# rtc_lcd.net
KiCad netlist of a schematic drawn in EAGLE
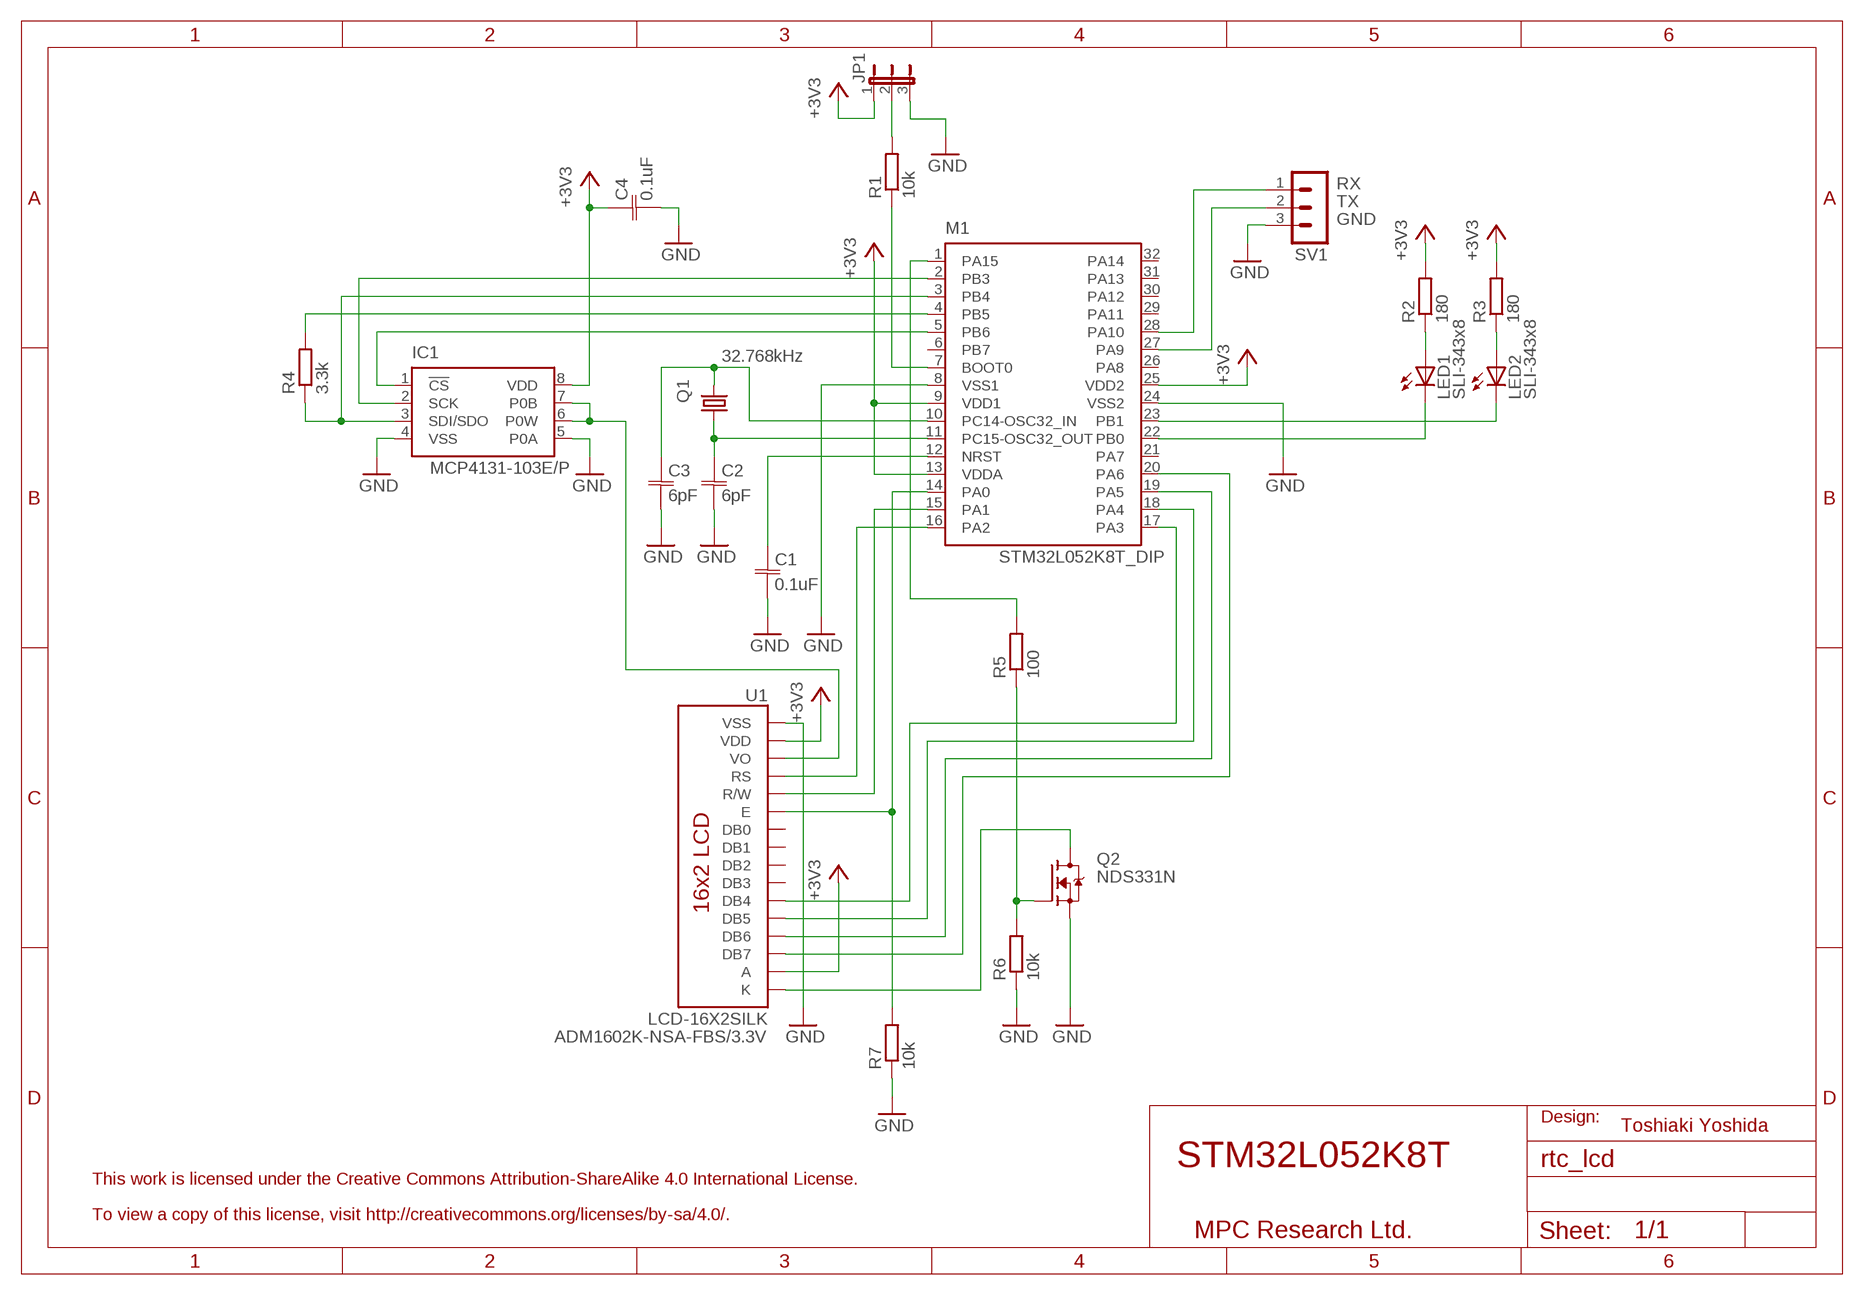
[diagram p0: schematic, sheet 1]

(export (version "E")
  (design (tool "Eeschema 10.0.6"))
  (components
    (comp (ref "C1")
      (value "0.1uF")
      (footprint "eagle-import:C050-024X044")
      (libsource (lib "eagle-import") (part "C-JIS050-024X044"))
    )
    (comp (ref "C2")
      (value "6pF")
      (footprint "eagle-import:C050-024X044")
      (libsource (lib "eagle-import") (part "C-JIS050-024X044"))
    )
    (comp (ref "C3")
      (value "6pF")
      (footprint "eagle-import:C050-024X044")
      (libsource (lib "eagle-import") (part "C-JIS050-024X044"))
    )
    (comp (ref "C4")
      (value "0.1uF")
      (footprint "eagle-import:C050-024X044")
      (libsource (lib "eagle-import") (part "C-JIS050-024X044"))
    )
    (comp (ref "IC1")
      (value "MCP4131-103E/P")
      (footprint "eagle-import:DIL8")
      (libsource (lib "eagle-import") (part "MCP4131/P-103E"))
    )
    (comp (ref "JP1")
      (value "JP2E")
      (footprint "eagle-import:JP2")
      (libsource (lib "eagle-import") (part "JP2E"))
    )
    (comp (ref "LED1")
      (value "SLI-343x8")
      (footprint "eagle-import:LED3MM")
      (libsource (lib "eagle-import") (part "LED3MM"))
    )
    (comp (ref "LED2")
      (value "SLI-343x8")
      (footprint "eagle-import:LED3MM")
      (libsource (lib "eagle-import") (part "LED3MM"))
    )
    (comp (ref "M1")
      (value "STM32L052K8T_DIP")
      (footprint "eagle-import:DIP32")
      (libsource (lib "eagle-import") (part "STM32L052K8T_DIP"))
    )
    (comp (ref "Q1")
      (value "32.768kHz")
      (footprint "eagle-import:TC26V")
      (libsource (lib "eagle-import") (part "CRYSTALTC26V"))
    )
    (comp (ref "Q2")
      (value "NDS331N")
      (footprint "eagle-import:SOT23")
      (libsource (lib "eagle-import") (part "NDS331N"))
    )
    (comp (ref "R1")
      (value "10k")
      (footprint "eagle-import:0207_2V")
      (libsource (lib "eagle-import") (part "R-EU_0207/2V"))
    )
    (comp (ref "R2")
      (value "180")
      (footprint "eagle-import:0207_2V")
      (libsource (lib "eagle-import") (part "R-EU_0207/2V"))
    )
    (comp (ref "R3")
      (value "180")
      (footprint "eagle-import:0207_2V")
      (libsource (lib "eagle-import") (part "R-EU_0207/2V"))
    )
    (comp (ref "R4")
      (value "3.3k")
      (footprint "eagle-import:0207_2V")
      (libsource (lib "eagle-import") (part "R-EU_0207/2V"))
    )
    (comp (ref "R5")
      (value "100")
      (footprint "eagle-import:0207_2V")
      (libsource (lib "eagle-import") (part "R-EU_0207/2V"))
    )
    (comp (ref "R6")
      (value "10k")
      (footprint "eagle-import:0207_2V")
      (libsource (lib "eagle-import") (part "R-EU_0207/2V"))
    )
    (comp (ref "R7")
      (value "10k")
      (footprint "eagle-import:0207_2V")
      (libsource (lib "eagle-import") (part "R-EU_0207/2V"))
    )
    (comp (ref "SV1")
      (value "MA03-1")
      (footprint "eagle-import:MA03-1")
      (libsource (lib "eagle-import") (part "MA03-1"))
    )
    (comp (ref "U1")
      (value "LCD-16X2SILK")
      (footprint "eagle-import:LCD-16X2")
      (libsource (lib "eagle-import") (part "LCD-16X2SILK"))
    )
  )
  (nets
    (net (code "1") (name "+3V3") (class "Default")
      (node (ref "C4") (pin "1") (pinfunction "1_1") (pintype "passive"))
      (node (ref "IC1") (pin "8") (pinfunction "VDD_8") (pintype "power_in"))
      (node (ref "JP1") (pin "1") (pinfunction "1_1") (pintype "passive"))
      (node (ref "M1") (pin "13") (pinfunction "VDDA_13") (pintype "power_in"))
      (node (ref "M1") (pin "25") (pinfunction "VDD2_25") (pintype "bidirectional"))
      (node (ref "M1") (pin "9") (pinfunction "VDD1_9") (pintype "power_in"))
      (node (ref "R2") (pin "2") (pinfunction "2_2") (pintype "passive"))
      (node (ref "R3") (pin "2") (pinfunction "2_2") (pintype "passive"))
      (node (ref "U1") (pin "15") (pinfunction "A_15") (pintype "power_in"))
      (node (ref "U1") (pin "2") (pinfunction "VDD_2") (pintype "power_in"))
    )
    (net (code "2") (name "GND") (class "Default")
      (node (ref "C1") (pin "2") (pinfunction "2_2") (pintype "passive"))
      (node (ref "C2") (pin "2") (pinfunction "2_2") (pintype "passive"))
      (node (ref "C3") (pin "2") (pinfunction "2_2") (pintype "passive"))
      (node (ref "C4") (pin "2") (pinfunction "2_2") (pintype "passive"))
      (node (ref "IC1") (pin "4") (pinfunction "VSS_4") (pintype "power_in"))
      (node (ref "IC1") (pin "5") (pinfunction "P0A_5") (pintype "passive"))
      (node (ref "JP1") (pin "3") (pinfunction "3_3") (pintype "passive"))
      (node (ref "M1") (pin "24") (pinfunction "VSS2_24") (pintype "power_in"))
      (node (ref "M1") (pin "8") (pinfunction "VSS1_8") (pintype "power_in"))
      (node (ref "Q2") (pin "2") (pinfunction "S_2") (pintype "passive"))
      (node (ref "R6") (pin "1") (pinfunction "1_1") (pintype "passive"))
      (node (ref "R7") (pin "1") (pinfunction "1_1") (pintype "passive"))
      (node (ref "SV1") (pin "3") (pinfunction "3_3") (pintype "passive"))
      (node (ref "U1") (pin "1") (pinfunction "VSS_1") (pintype "power_in"))
    )
    (net (code "3") (name "Net-(IC1-P0B)") (class "Default")
      (node (ref "IC1") (pin "6") (pinfunction "P0W_6") (pintype "passive"))
      (node (ref "IC1") (pin "7") (pinfunction "P0B_7") (pintype "passive"))
      (node (ref "U1") (pin "3") (pinfunction "VO_3") (pintype "bidirectional"))
    )
    (net (code "4") (name "Net-(IC1-SCK)") (class "Default")
      (node (ref "IC1") (pin "2") (pinfunction "SCK_2") (pintype "input"))
      (node (ref "M1") (pin "2") (pinfunction "PB3_2") (pintype "bidirectional"))
    )
    (net (code "5") (name "Net-(IC1-SDI{slash}SDO)") (class "Default")
      (node (ref "IC1") (pin "3") (pinfunction "SDI/SDO_3") (pintype "bidirectional"))
      (node (ref "M1") (pin "3") (pinfunction "PB4_3") (pintype "bidirectional"))
      (node (ref "R4") (pin "1") (pinfunction "1_1") (pintype "passive"))
    )
    (net (code "6") (name "Net-(IC1-~{CS})") (class "Default")
      (node (ref "IC1") (pin "1") (pinfunction "~{CS}_1") (pintype "input"))
      (node (ref "M1") (pin "5") (pinfunction "PB6_5") (pintype "bidirectional"))
    )
    (net (code "7") (name "Net-(JP1-Pad2)") (class "Default")
      (node (ref "JP1") (pin "2") (pinfunction "2_2") (pintype "passive"))
      (node (ref "R1") (pin "2") (pinfunction "2_2") (pintype "passive"))
    )
    (net (code "8") (name "Net-(LED1-C)") (class "Default")
      (node (ref "LED1") (pin "K") (pinfunction "C_K") (pintype "passive"))
      (node (ref "M1") (pin "22") (pinfunction "PB0_22") (pintype "bidirectional"))
    )
    (net (code "9") (name "Net-(LED1-PadA)") (class "Default")
      (node (ref "LED1") (pin "A") (pinfunction "A_A") (pintype "passive"))
      (node (ref "R2") (pin "1") (pinfunction "1_1") (pintype "passive"))
    )
    (net (code "10") (name "Net-(LED2-C)") (class "Default")
      (node (ref "LED2") (pin "K") (pinfunction "C_K") (pintype "passive"))
      (node (ref "M1") (pin "23") (pinfunction "PB1_23") (pintype "bidirectional"))
    )
    (net (code "11") (name "Net-(LED2-PadA)") (class "Default")
      (node (ref "LED2") (pin "A") (pinfunction "A_A") (pintype "passive"))
      (node (ref "R3") (pin "1") (pinfunction "1_1") (pintype "passive"))
    )
    (net (code "12") (name "Net-(M1-BOOT0)") (class "Default")
      (node (ref "M1") (pin "7") (pinfunction "BOOT0_7") (pintype "bidirectional"))
      (node (ref "R1") (pin "1") (pinfunction "1_1") (pintype "passive"))
    )
    (net (code "13") (name "Net-(M1-NRST)") (class "Default")
      (node (ref "C1") (pin "1") (pinfunction "1_1") (pintype "passive"))
      (node (ref "M1") (pin "12") (pinfunction "NRST_12") (pintype "bidirectional"))
    )
    (net (code "14") (name "Net-(M1-PA0)") (class "Default")
      (node (ref "M1") (pin "14") (pinfunction "PA0_14") (pintype "bidirectional"))
      (node (ref "R7") (pin "2") (pinfunction "2_2") (pintype "passive"))
      (node (ref "U1") (pin "6") (pinfunction "E_6") (pintype "input"))
    )
    (net (code "15") (name "Net-(M1-PA1)") (class "Default")
      (node (ref "M1") (pin "15") (pinfunction "PA1_15") (pintype "bidirectional"))
      (node (ref "U1") (pin "5") (pinfunction "R/W_5") (pintype "input"))
    )
    (net (code "16") (name "Net-(M1-PA2)") (class "Default")
      (node (ref "M1") (pin "16") (pinfunction "PA2_16") (pintype "bidirectional"))
      (node (ref "U1") (pin "4") (pinfunction "RS_4") (pintype "input"))
    )
    (net (code "17") (name "Net-(M1-PA3)") (class "Default")
      (node (ref "M1") (pin "17") (pinfunction "PA3_17") (pintype "bidirectional"))
      (node (ref "U1") (pin "11") (pinfunction "DB4_11") (pintype "bidirectional"))
    )
    (net (code "18") (name "Net-(M1-PA4)") (class "Default")
      (node (ref "M1") (pin "18") (pinfunction "PA4_18") (pintype "bidirectional"))
      (node (ref "U1") (pin "12") (pinfunction "DB5_12") (pintype "bidirectional"))
    )
    (net (code "19") (name "Net-(M1-PA5)") (class "Default")
      (node (ref "M1") (pin "19") (pinfunction "PA5_19") (pintype "bidirectional"))
      (node (ref "U1") (pin "13") (pinfunction "DB6_13") (pintype "bidirectional"))
    )
    (net (code "20") (name "Net-(M1-PA6)") (class "Default")
      (node (ref "M1") (pin "20") (pinfunction "PA6_20") (pintype "bidirectional"))
      (node (ref "U1") (pin "14") (pinfunction "DB7_14") (pintype "bidirectional"))
    )
    (net (code "21") (name "Net-(M1-PA9)") (class "Default")
      (node (ref "M1") (pin "27") (pinfunction "PA9_27") (pintype "bidirectional"))
      (node (ref "SV1") (pin "2") (pinfunction "2_2") (pintype "passive"))
    )
    (net (code "22") (name "Net-(M1-PA10)") (class "Default")
      (node (ref "M1") (pin "28") (pinfunction "PA10_28") (pintype "bidirectional"))
      (node (ref "SV1") (pin "1") (pinfunction "1_1") (pintype "passive"))
    )
    (net (code "23") (name "Net-(M1-PA15)") (class "Default")
      (node (ref "M1") (pin "1") (pinfunction "PA15_1") (pintype "bidirectional"))
      (node (ref "R5") (pin "2") (pinfunction "2_2") (pintype "passive"))
    )
    (net (code "24") (name "Net-(M1-PB5)") (class "Default")
      (node (ref "M1") (pin "4") (pinfunction "PB5_4") (pintype "bidirectional"))
      (node (ref "R4") (pin "2") (pinfunction "2_2") (pintype "passive"))
    )
    (net (code "25") (name "Net-(M1-PC14-OSC32_IN)") (class "Default")
      (node (ref "C3") (pin "1") (pinfunction "1_1") (pintype "passive"))
      (node (ref "M1") (pin "10") (pinfunction "PC14-OSC32_IN_10") (pintype "bidirectional"))
      (node (ref "Q1") (pin "2") (pinfunction "2_2") (pintype "passive"))
    )
    (net (code "26") (name "Net-(M1-PC15-OSC32_OUT)") (class "Default")
      (node (ref "C2") (pin "1") (pinfunction "1_1") (pintype "passive"))
      (node (ref "M1") (pin "11") (pinfunction "PC15-OSC32_OUT_11") (pintype "bidirectional"))
      (node (ref "Q1") (pin "1") (pinfunction "1_1") (pintype "passive"))
    )
    (net (code "27") (name "Net-(Q2-D)") (class "Default")
      (node (ref "Q2") (pin "3") (pinfunction "D_3") (pintype "passive"))
      (node (ref "U1") (pin "16") (pinfunction "K_16") (pintype "power_in"))
    )
    (net (code "28") (name "Net-(Q2-G)") (class "Default")
      (node (ref "Q2") (pin "1") (pinfunction "G_1") (pintype "passive"))
      (node (ref "R5") (pin "1") (pinfunction "1_1") (pintype "passive"))
      (node (ref "R6") (pin "2") (pinfunction "2_2") (pintype "passive"))
    )
    (net (code "29") (name "unconnected-(M1-PA7-Pad21)") (class "Default")
      (node (ref "M1") (pin "21") (pinfunction "PA7_21") (pintype "bidirectional"))
    )
    (net (code "30") (name "unconnected-(M1-PA8-Pad26)") (class "Default")
      (node (ref "M1") (pin "26") (pinfunction "PA8_26") (pintype "bidirectional"))
    )
    (net (code "31") (name "unconnected-(M1-PA11-Pad29)") (class "Default")
      (node (ref "M1") (pin "29") (pinfunction "PA11_29") (pintype "bidirectional"))
    )
    (net (code "32") (name "unconnected-(M1-PA12-Pad30)") (class "Default")
      (node (ref "M1") (pin "30") (pinfunction "PA12_30") (pintype "bidirectional"))
    )
    (net (code "33") (name "unconnected-(M1-PA13-Pad31)") (class "Default")
      (node (ref "M1") (pin "31") (pinfunction "PA13_31") (pintype "bidirectional"))
    )
    (net (code "34") (name "unconnected-(M1-PA14-Pad32)") (class "Default")
      (node (ref "M1") (pin "32") (pinfunction "PA14_32") (pintype "bidirectional"))
    )
    (net (code "35") (name "unconnected-(M1-PB7-Pad6)") (class "Default")
      (node (ref "M1") (pin "6") (pinfunction "PB7_6") (pintype "bidirectional"))
    )
    (net (code "36") (name "unconnected-(U1-DB0-Pad7)") (class "Default")
      (node (ref "U1") (pin "7") (pinfunction "DB0_7") (pintype "bidirectional"))
    )
    (net (code "37") (name "unconnected-(U1-DB1-Pad8)") (class "Default")
      (node (ref "U1") (pin "8") (pinfunction "DB1_8") (pintype "bidirectional"))
    )
    (net (code "38") (name "unconnected-(U1-DB2-Pad9)") (class "Default")
      (node (ref "U1") (pin "9") (pinfunction "DB2_9") (pintype "bidirectional"))
    )
    (net (code "39") (name "unconnected-(U1-DB3-Pad10)") (class "Default")
      (node (ref "U1") (pin "10") (pinfunction "DB3_10") (pintype "bidirectional"))
    )
  )
)
